# E-P-020-R2_0.net
KiCad netlist of a schematic drawn in EAGLE
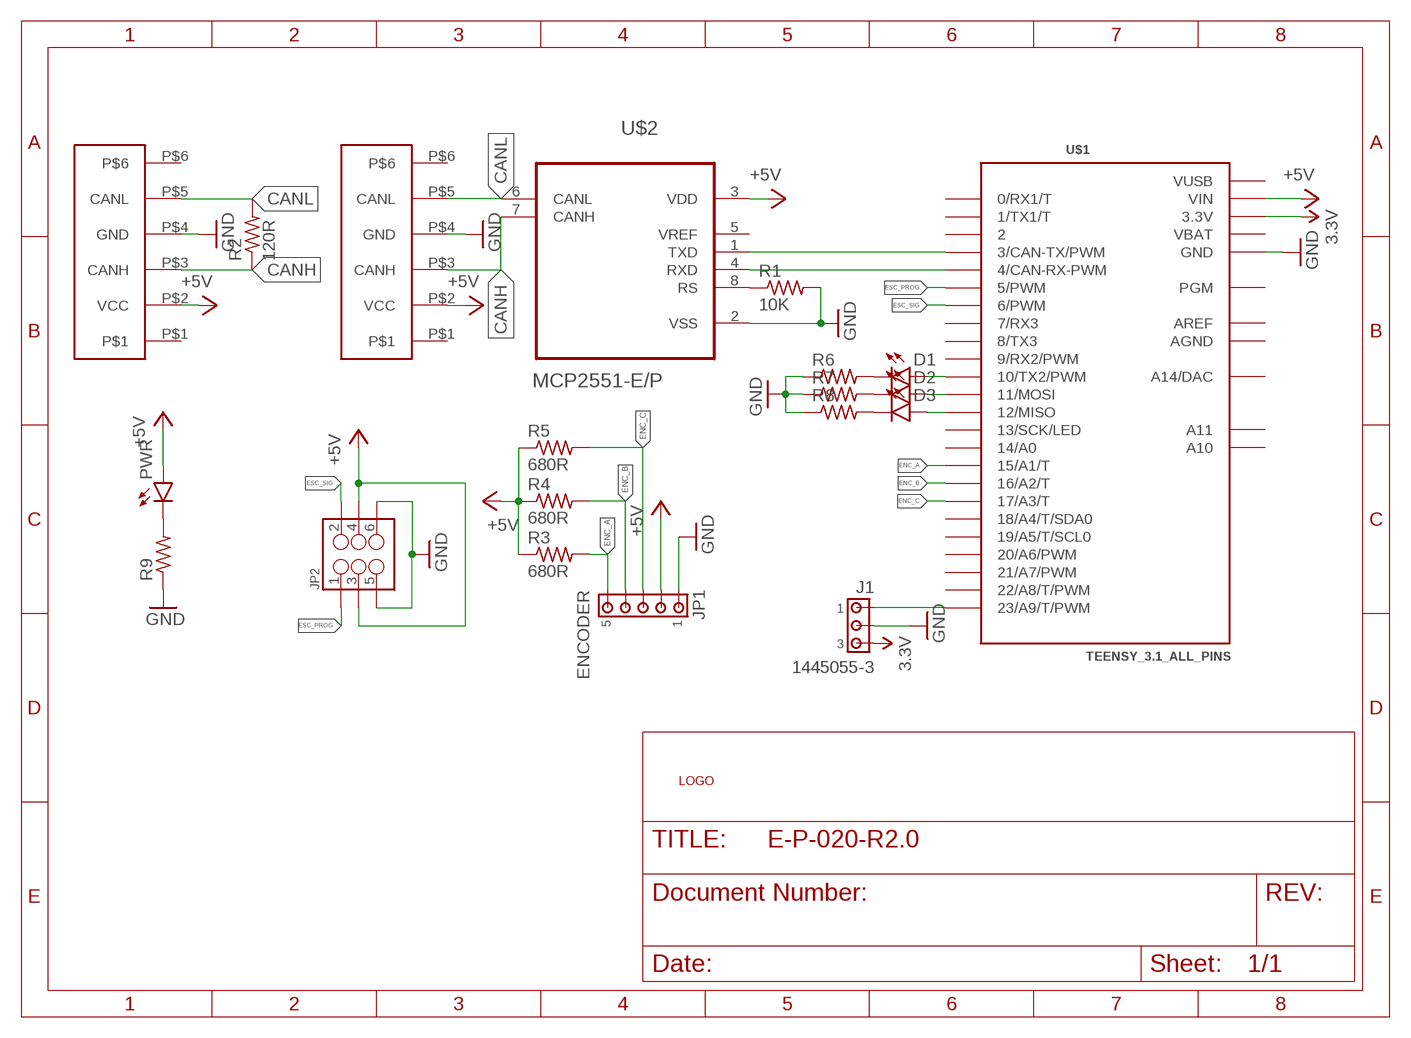
[diagram p0: schematic, sheet 1]

(export (version "E")
  (design (tool "Eeschema 10.0.6"))
  (components
    (comp (ref "D1")
      (value "BLUE")
      (footprint "eagle-import:LED-1206")
      (libsource (lib "eagle-import") (part "LED-BLUE1206"))
    )
    (comp (ref "D2")
      (value "BLUE")
      (footprint "eagle-import:LED-1206")
      (libsource (lib "eagle-import") (part "LED-BLUE1206"))
    )
    (comp (ref "D3")
      (value "BLUE")
      (footprint "eagle-import:LED-1206")
      (libsource (lib "eagle-import") (part "LED-BLUE1206"))
    )
    (comp (ref "J1")
      (value "1445055-3")
      (footprint "eagle-import:1445055-3")
      (libsource (lib "eagle-import") (part "1445055-3"))
    )
    (comp (ref "JP1")
      (value "ENCODER")
      (footprint "eagle-import:1445055-5")
      (libsource (lib "eagle-import") (part "1445055-5"))
    )
    (comp (ref "JP2")
      (value "M03X2POGO_PINS")
      (footprint "eagle-import:2X3_POGO")
      (libsource (lib "eagle-import") (part "M03X2POGO_PINS"))
    )
    (comp (ref "PWR")
      (value "BLUE")
      (footprint "eagle-import:LED-1206")
      (libsource (lib "eagle-import") (part "LED-BLUE1206"))
    )
    (comp (ref "R1")
      (value "10K")
      (footprint "eagle-import:R0805")
      (libsource (lib "eagle-import") (part "R-US_R0805"))
    )
    (comp (ref "R2")
      (value "120R")
      (footprint "eagle-import:M1206")
      (libsource (lib "eagle-import") (part "R-US_M1206"))
    )
    (comp (ref "R3")
      (value "680R")
      (footprint "eagle-import:M0805")
      (libsource (lib "eagle-import") (part "R-US_M0805"))
    )
    (comp (ref "R4")
      (value "680R")
      (footprint "eagle-import:M0805")
      (libsource (lib "eagle-import") (part "R-US_M0805"))
    )
    (comp (ref "R5")
      (value "680R")
      (footprint "eagle-import:M0805")
      (libsource (lib "eagle-import") (part "R-US_M0805"))
    )
    (comp (ref "R6")
      (value "R-US_M1206")
      (footprint "eagle-import:M1206")
      (libsource (lib "eagle-import") (part "resistor_R-US_M1206"))
    )
    (comp (ref "R7")
      (value "R-US_M1206")
      (footprint "eagle-import:M1206")
      (libsource (lib "eagle-import") (part "resistor_R-US_M1206"))
    )
    (comp (ref "R8")
      (value "R-US_M1206")
      (footprint "eagle-import:M1206")
      (libsource (lib "eagle-import") (part "resistor_R-US_M1206"))
    )
    (comp (ref "R9")
      (value "R-US_M1206")
      (footprint "eagle-import:M1206")
      (libsource (lib "eagle-import") (part "resistor_R-US_M1206"))
    )
    (comp (ref "U$1")
      (value "TEENSY_3.1_ALL_PINS")
      (footprint "eagle-import:TEENSY3-ALL_PINS")
      (libsource (lib "eagle-import") (part "TEENSY_3.1_ALL_PINS"))
    )
    (comp (ref "U$2")
      (value "MCP2551-E/P")
      (footprint "eagle-import:DIP254P762X432-8")
      (libsource (lib "eagle-import") (part "MCP2551-E/P"))
    )
    (comp (ref "U$3")
      (value "CAN_6P6C")
      (footprint "eagle-import:CAN_6P6C")
      (libsource (lib "eagle-import") (part "CAN_6P6C"))
    )
    (comp (ref "U$4")
      (value "LOGO")
      (footprint "eagle-import:LOGO")
      (libsource (lib "eagle-import") (part "LOGO"))
    )
    (comp (ref "U$5")
      (value "CAN_6P6C")
      (footprint "eagle-import:CAN_6P6C")
      (libsource (lib "eagle-import") (part "CAN_6P6C"))
    )
  )
  (nets
    (net (code "1") (name "+5V") (class "Default")
      (node (ref "JP1") (pin "2") (pinfunction "2_2") (pintype "passive"))
      (node (ref "JP2") (pin "P$3") (pinfunction "3_P$3") (pintype "bidirectional"))
      (node (ref "JP2") (pin "P$4") (pinfunction "4_P$4") (pintype "bidirectional"))
      (node (ref "PWR") (pin "A") (pinfunction "A_A") (pintype "passive"))
      (node (ref "R3") (pin "1") (pinfunction "1_1") (pintype "passive"))
      (node (ref "R4") (pin "1") (pinfunction "1_1") (pintype "passive"))
      (node (ref "R5") (pin "1") (pinfunction "1_1") (pintype "passive"))
      (node (ref "U$1") (pin "VIN") (pinfunction "VIN_VIN") (pintype "power_in"))
      (node (ref "U$2") (pin "3") (pinfunction "VDD_3") (pintype "power_in"))
      (node (ref "U$3") (pin "P$2") (pinfunction "VCC_P$2") (pintype "bidirectional"))
      (node (ref "U$5") (pin "P$2") (pinfunction "VCC_P$2") (pintype "bidirectional"))
    )
    (net (code "2") (name "/AGND") (class "Default")
      (node (ref "U$1") (pin "AGND") (pinfunction "AGND_AGND") (pintype "power_in"))
    )
    (net (code "3") (name "/AREF") (class "Default")
      (node (ref "U$1") (pin "AREF") (pinfunction "AREF_AREF") (pintype "power_in"))
    )
    (net (code "4") (name "/VBAT") (class "Default")
      (node (ref "U$1") (pin "VBAT") (pinfunction "VBAT_VBAT") (pintype "power_in"))
    )
    (net (code "5") (name "/VUSB") (class "Default")
      (node (ref "U$1") (pin "VUSB") (pinfunction "VUSB_VUSB") (pintype "power_in"))
    )
    (net (code "6") (name "3.3V") (class "Default")
      (node (ref "J1") (pin "3") (pinfunction "3_3") (pintype "passive"))
      (node (ref "U$1") (pin "3.3V") (pinfunction "3.3V_3.3V") (pintype "power_in"))
      (node (ref "U$1") (pin "3.3V1") (pinfunction "3.3V_3.3V1") (pintype "power_in"))
    )
    (net (code "7") (name "CANH") (class "Default")
      (node (ref "R2") (pin "1") (pinfunction "1_1") (pintype "passive"))
      (node (ref "U$2") (pin "7") (pinfunction "CANH_7") (pintype "output"))
      (node (ref "U$3") (pin "P$3") (pinfunction "CANH_P$3") (pintype "bidirectional"))
      (node (ref "U$5") (pin "P$3") (pinfunction "CANH_P$3") (pintype "bidirectional"))
    )
    (net (code "8") (name "CANL") (class "Default")
      (node (ref "R2") (pin "2") (pinfunction "2_2") (pintype "passive"))
      (node (ref "U$2") (pin "6") (pinfunction "CANL_6") (pintype "output"))
      (node (ref "U$3") (pin "P$5") (pinfunction "CANL_P$5") (pintype "bidirectional"))
      (node (ref "U$5") (pin "P$5") (pinfunction "CANL_P$5") (pintype "bidirectional"))
    )
    (net (code "9") (name "ENC_A") (class "Default")
      (node (ref "JP1") (pin "5") (pinfunction "5_5") (pintype "passive"))
      (node (ref "R3") (pin "2") (pinfunction "2_2") (pintype "passive"))
      (node (ref "U$1") (pin "15/A1") (pinfunction "15/A1/T_15/A1") (pintype "bidirectional"))
    )
    (net (code "10") (name "ENC_B") (class "Default")
      (node (ref "JP1") (pin "4") (pinfunction "4_4") (pintype "passive"))
      (node (ref "R4") (pin "2") (pinfunction "2_2") (pintype "passive"))
      (node (ref "U$1") (pin "16/A2") (pinfunction "16/A2/T_16/A2") (pintype "bidirectional"))
    )
    (net (code "11") (name "ENC_C") (class "Default")
      (node (ref "JP1") (pin "3") (pinfunction "3_3") (pintype "passive"))
      (node (ref "R5") (pin "2") (pinfunction "2_2") (pintype "passive"))
      (node (ref "U$1") (pin "17/A3") (pinfunction "17/A3/T_17/A3") (pintype "bidirectional"))
    )
    (net (code "12") (name "ESC_PROG") (class "Default")
      (node (ref "JP2") (pin "P$1") (pinfunction "1_P$1") (pintype "bidirectional"))
      (node (ref "U$1") (pin "5") (pinfunction "5/PWM_5") (pintype "bidirectional"))
    )
    (net (code "13") (name "ESC_SIG") (class "Default")
      (node (ref "JP2") (pin "P$2") (pinfunction "2_P$2") (pintype "bidirectional"))
      (node (ref "U$1") (pin "6") (pinfunction "6/PWM_6") (pintype "bidirectional"))
    )
    (net (code "14") (name "GND") (class "Default")
      (node (ref "J1") (pin "2") (pinfunction "2_2") (pintype "passive"))
      (node (ref "JP1") (pin "1") (pinfunction "1_1") (pintype "passive"))
      (node (ref "JP2") (pin "P$5") (pinfunction "5_P$5") (pintype "bidirectional"))
      (node (ref "JP2") (pin "P$6") (pinfunction "6_P$6") (pintype "bidirectional"))
      (node (ref "R1") (pin "2") (pinfunction "2_2") (pintype "passive"))
      (node (ref "R6") (pin "1") (pinfunction "1_1") (pintype "passive"))
      (node (ref "R7") (pin "1") (pinfunction "1_1") (pintype "passive"))
      (node (ref "R8") (pin "1") (pinfunction "1_1") (pintype "passive"))
      (node (ref "R9") (pin "1") (pinfunction "1_1") (pintype "passive"))
      (node (ref "U$1") (pin "GND") (pinfunction "GND_GND") (pintype "power_in"))
      (node (ref "U$1") (pin "GND1") (pinfunction "GND_GND1") (pintype "power_in"))
      (node (ref "U$2") (pin "2") (pinfunction "VSS_2") (pintype "passive"))
      (node (ref "U$3") (pin "P$4") (pinfunction "GND_P$4") (pintype "bidirectional"))
      (node (ref "U$5") (pin "P$4") (pinfunction "GND_P$4") (pintype "bidirectional"))
    )
    (net (code "15") (name "Net-(D1-PadC)") (class "Default")
      (node (ref "D1") (pin "C") (pinfunction "C_C") (pintype "passive"))
      (node (ref "R6") (pin "2") (pinfunction "2_2") (pintype "passive"))
    )
    (net (code "16") (name "Net-(D2-PadC)") (class "Default")
      (node (ref "D2") (pin "C") (pinfunction "C_C") (pintype "passive"))
      (node (ref "R7") (pin "2") (pinfunction "2_2") (pintype "passive"))
    )
    (net (code "17") (name "Net-(D3-PadC)") (class "Default")
      (node (ref "D3") (pin "C") (pinfunction "C_C") (pintype "passive"))
      (node (ref "R8") (pin "2") (pinfunction "2_2") (pintype "passive"))
    )
    (net (code "18") (name "Net-(PWR-PadC)") (class "Default")
      (node (ref "PWR") (pin "C") (pinfunction "C_C") (pintype "passive"))
      (node (ref "R9") (pin "2") (pinfunction "2_2") (pintype "passive"))
    )
    (net (code "19") (name "Net-(U$1-3{slash}CAN-TX{slash}PWM)") (class "Default")
      (node (ref "U$1") (pin "3") (pinfunction "3/CAN-TX/PWM_3") (pintype "bidirectional"))
      (node (ref "U$2") (pin "1") (pinfunction "TXD_1") (pintype "input"))
    )
    (net (code "20") (name "Net-(U$1-4{slash}CAN-RX-PWM)") (class "Default")
      (node (ref "U$1") (pin "4") (pinfunction "4/CAN-RX-PWM_4") (pintype "bidirectional"))
      (node (ref "U$2") (pin "4") (pinfunction "RXD_4") (pintype "input"))
    )
    (net (code "21") (name "Net-(U$1-10{slash}TX2{slash}PWM)") (class "Default")
      (node (ref "D1") (pin "A") (pinfunction "A_A") (pintype "passive"))
      (node (ref "U$1") (pin "10") (pinfunction "10/TX2/PWM_10") (pintype "bidirectional"))
    )
    (net (code "22") (name "Net-(U$1-11{slash}MOSI)") (class "Default")
      (node (ref "D2") (pin "A") (pinfunction "A_A") (pintype "passive"))
      (node (ref "U$1") (pin "11") (pinfunction "11/MOSI_11") (pintype "bidirectional"))
    )
    (net (code "23") (name "Net-(U$1-12{slash}MISO)") (class "Default")
      (node (ref "D3") (pin "A") (pinfunction "A_A") (pintype "passive"))
      (node (ref "U$1") (pin "12") (pinfunction "12/MISO_12") (pintype "bidirectional"))
    )
    (net (code "24") (name "Net-(U$1-23{slash}A9{slash}T{slash}PWM)") (class "Default")
      (node (ref "J1") (pin "1") (pinfunction "1_1") (pintype "passive"))
      (node (ref "U$1") (pin "23/A9") (pinfunction "23/A9/T/PWM_23/A9") (pintype "bidirectional"))
    )
    (net (code "25") (name "Net-(U$2-RS)") (class "Default")
      (node (ref "R1") (pin "1") (pinfunction "1_1") (pintype "passive"))
      (node (ref "U$2") (pin "8") (pinfunction "RS_8") (pintype "input"))
    )
    (net (code "26") (name "unconnected-(U$1-0{slash}RX1{slash}T-Pad0)") (class "Default")
      (node (ref "U$1") (pin "0") (pinfunction "0/RX1/T_0") (pintype "bidirectional"))
    )
    (net (code "27") (name "unconnected-(U$1-1{slash}TX1{slash}T-Pad1)") (class "Default")
      (node (ref "U$1") (pin "1") (pinfunction "1/TX1/T_1") (pintype "bidirectional"))
    )
    (net (code "28") (name "unconnected-(U$1-7{slash}RX3-Pad7)") (class "Default")
      (node (ref "U$1") (pin "7") (pinfunction "7/RX3_7") (pintype "bidirectional"))
    )
    (net (code "29") (name "unconnected-(U$1-8{slash}TX3-Pad8)") (class "Default")
      (node (ref "U$1") (pin "8") (pinfunction "8/TX3_8") (pintype "bidirectional"))
    )
    (net (code "30") (name "unconnected-(U$1-9{slash}RX2{slash}PWM-Pad9)") (class "Default")
      (node (ref "U$1") (pin "9") (pinfunction "9/RX2/PWM_9") (pintype "bidirectional"))
    )
    (net (code "31") (name "unconnected-(U$1-13{slash}SCK{slash}LED-Pad13)") (class "Default")
      (node (ref "U$1") (pin "13") (pinfunction "13/SCK/LED_13") (pintype "bidirectional"))
    )
    (net (code "32") (name "unconnected-(U$1-18{slash}A4{slash}T{slash}SDA0-Pad18{slash}A4)") (class "Default")
      (node (ref "U$1") (pin "18/A4") (pinfunction "18/A4/T/SDA0_18/A4") (pintype "bidirectional"))
    )
    (net (code "33") (name "unconnected-(U$1-19{slash}A5{slash}T{slash}SCL0-Pad19{slash}A5)") (class "Default")
      (node (ref "U$1") (pin "19/A5") (pinfunction "19/A5/T/SCL0_19/A5") (pintype "bidirectional"))
    )
    (net (code "34") (name "unconnected-(U$1-20{slash}A6{slash}PWM-Pad20{slash}A6)") (class "Default")
      (node (ref "U$1") (pin "20/A6") (pinfunction "20/A6/PWM_20/A6") (pintype "bidirectional"))
    )
    (net (code "35") (name "unconnected-(U$1-21{slash}A7{slash}PWM-Pad21{slash}A7)") (class "Default")
      (node (ref "U$1") (pin "21/A7") (pinfunction "21/A7/PWM_21/A7") (pintype "bidirectional"))
    )
    (net (code "36") (name "unconnected-(U$1-22{slash}A8{slash}T{slash}PWM-Pad22{slash}A8)") (class "Default")
      (node (ref "U$1") (pin "22/A8") (pinfunction "22/A8/T/PWM_22/A8") (pintype "bidirectional"))
    )
    (net (code "37") (name "unconnected-(U$1-A14{slash}DAC-PadRESET{slash}DAC)") (class "Default")
      (node (ref "U$1") (pin "RESET/DAC") (pinfunction "A14/DAC_RESET/DAC") (pintype "bidirectional"))
    )
    (net (code "38") (name "unconnected-(U$1-Pad2)") (class "Default")
      (node (ref "U$1") (pin "2") (pinfunction "2_2") (pintype "bidirectional"))
    )
    (net (code "39") (name "unconnected-(U$1-Pad14{slash}A0)") (class "Default")
      (node (ref "U$1") (pin "14/A0") (pinfunction "14/A0_14/A0") (pintype "bidirectional"))
    )
    (net (code "40") (name "unconnected-(U$1-PadA10)") (class "Default")
      (node (ref "U$1") (pin "A10") (pinfunction "A10_A10") (pintype "bidirectional"))
    )
    (net (code "41") (name "unconnected-(U$1-PadA11)") (class "Default")
      (node (ref "U$1") (pin "A11") (pinfunction "A11_A11") (pintype "bidirectional"))
    )
    (net (code "42") (name "unconnected-(U$1-PadPGM)") (class "Default")
      (node (ref "U$1") (pin "PGM") (pinfunction "PGM_PGM") (pintype "bidirectional"))
    )
    (net (code "43") (name "unconnected-(U$2-VREF-Pad5)") (class "Default")
      (node (ref "U$2") (pin "5") (pinfunction "VREF_5") (pintype "input"))
    )
    (net (code "44") (name "unconnected-(U$3-PadP$1)") (class "Default")
      (node (ref "U$3") (pin "P$1") (pinfunction "P$1_P$1") (pintype "bidirectional"))
    )
    (net (code "45") (name "unconnected-(U$3-PadP$6)") (class "Default")
      (node (ref "U$3") (pin "P$6") (pinfunction "P$6_P$6") (pintype "bidirectional"))
    )
    (net (code "46") (name "unconnected-(U$5-PadP$1)") (class "Default")
      (node (ref "U$5") (pin "P$1") (pinfunction "P$1_P$1") (pintype "bidirectional"))
    )
    (net (code "47") (name "unconnected-(U$5-PadP$6)") (class "Default")
      (node (ref "U$5") (pin "P$6") (pinfunction "P$6_P$6") (pintype "bidirectional"))
    )
  )
)
